# LightLog_SMD_0_6.net
KiCad netlist of a schematic drawn in EAGLE
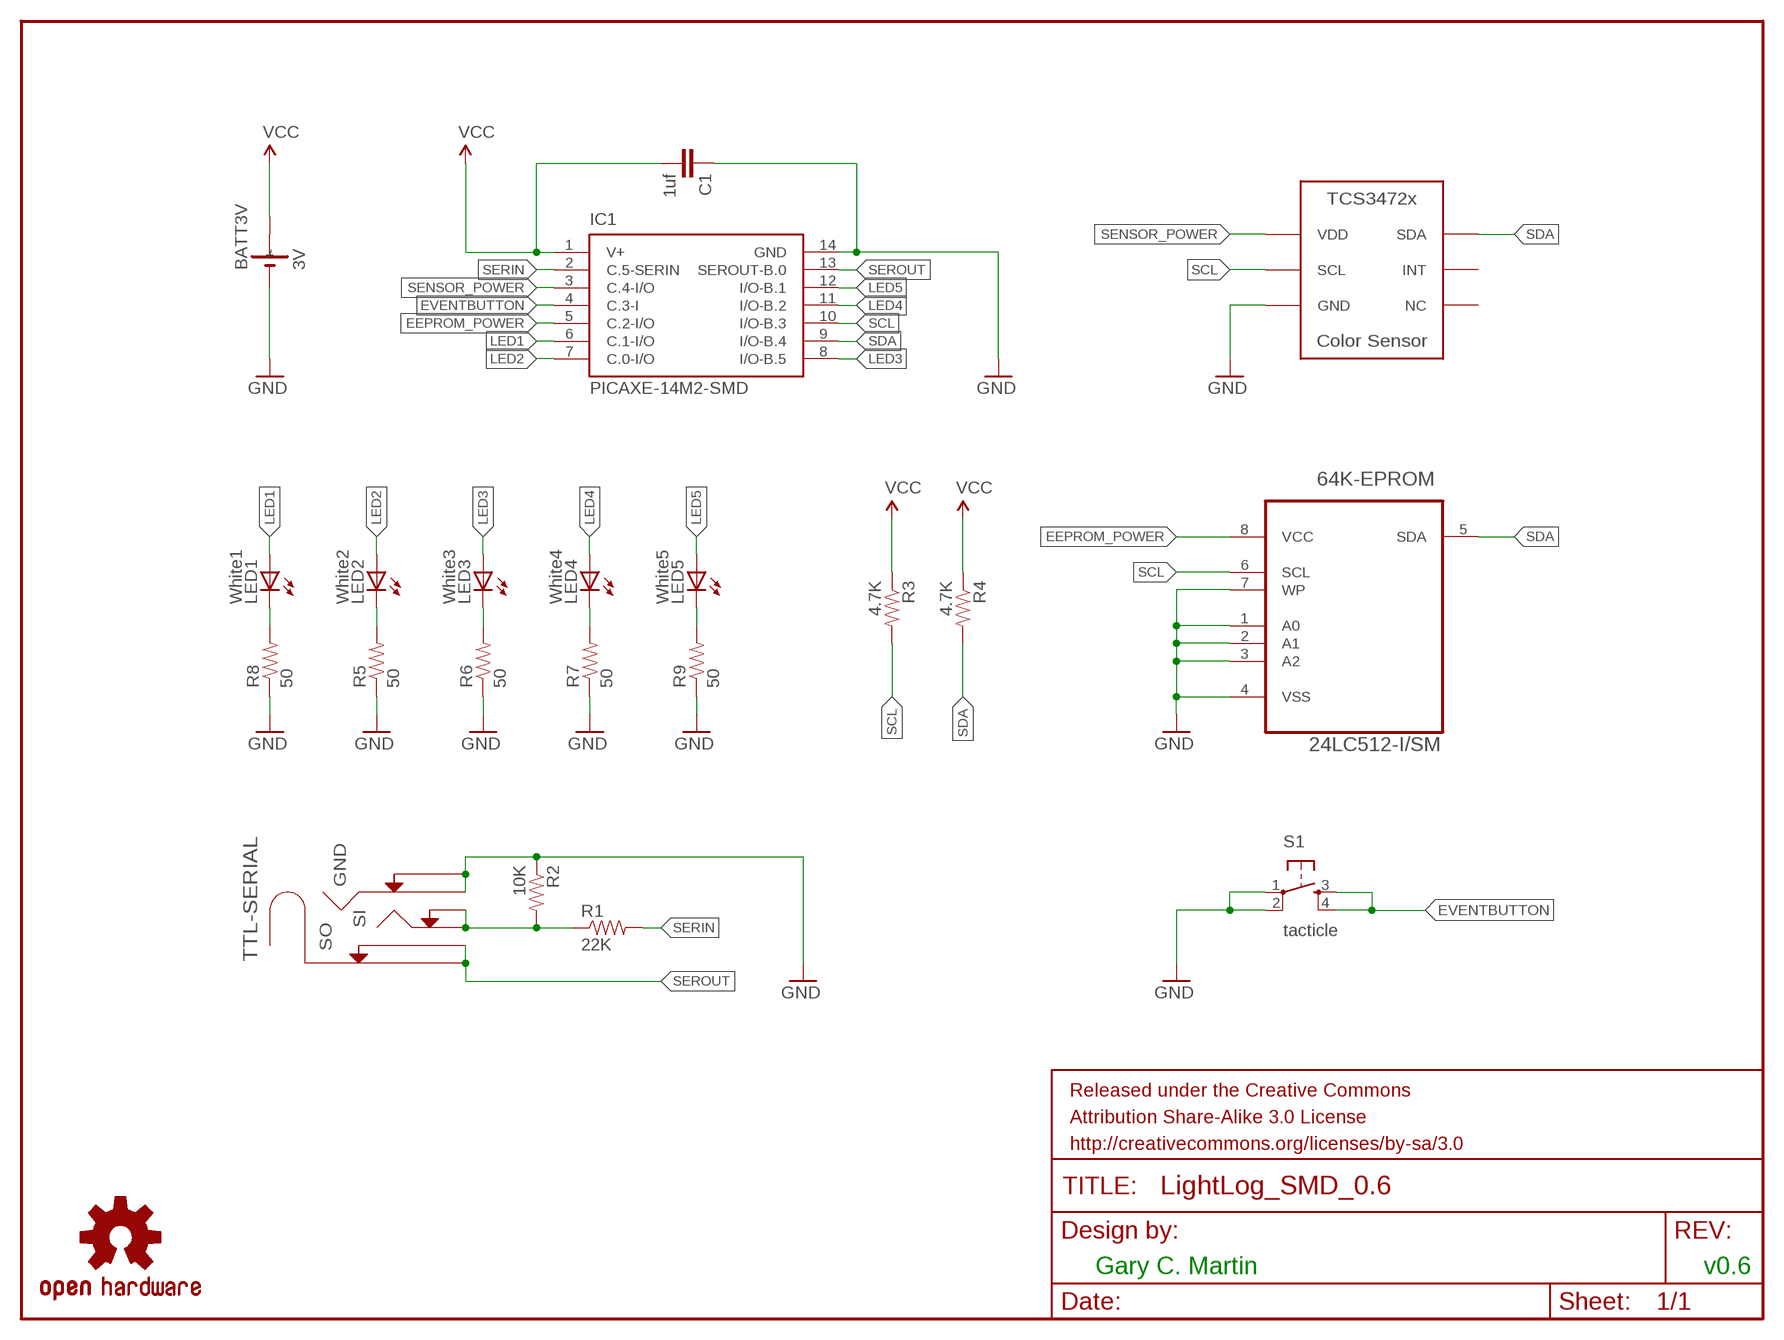
[diagram p0: schematic, sheet 1]

(export (version "E")
  (design (tool "Eeschema 10.0.6"))
  (components
    (comp (ref "64K-EPROM")
      (value "24LC512-I/SM")
      (footprint "eagle-import:SOIC127P794X203-8N")
      (libsource (lib "eagle-import") (part "24LC512-I/SM"))
    )
    (comp (ref "BATT3V")
      (value "3V")
      (footprint "eagle-import:BAT-HLD-001-CR2032-SMD")
      (libsource (lib "eagle-import") (part "BAT-HLD-001-CR2032"))
    )
    (comp (ref "C1")
      (value "1uf")
      (footprint "eagle-import:0805")
      (libsource (lib "eagle-import") (part "CAP0805"))
    )
    (comp (ref "IC1")
      (value "PICAXE-14M2-SMD")
      (footprint "eagle-import:SOIC14")
      (libsource (lib "eagle-import") (part "PICAXE-14M2-SMD"))
    )
    (comp (ref "LED1")
      (value "White1")
      (footprint "eagle-import:LED-1206")
      (libsource (lib "eagle-import") (part "LED1206"))
    )
    (comp (ref "LED2")
      (value "White2")
      (footprint "eagle-import:LED-1206")
      (libsource (lib "eagle-import") (part "LED1206"))
    )
    (comp (ref "LED3")
      (value "White3")
      (footprint "eagle-import:LED-1206")
      (libsource (lib "eagle-import") (part "LED1206"))
    )
    (comp (ref "LED4")
      (value "White4")
      (footprint "eagle-import:LED-1206")
      (libsource (lib "eagle-import") (part "LED1206"))
    )
    (comp (ref "LED5")
      (value "White5")
      (footprint "eagle-import:LED-1206")
      (libsource (lib "eagle-import") (part "LED1206"))
    )
    (comp (ref "LOGO1")
      (value "OSHW-LOGOS")
      (footprint "eagle-import:OSHW-LOGO-S")
      (libsource (lib "eagle-import") (part "OSHW-LOGOS"))
    )
    (comp (ref "R1")
      (value "22K")
      (footprint "eagle-import:0805")
      (libsource (lib "eagle-import") (part "RESISTOR0805-RES"))
    )
    (comp (ref "R2")
      (value "10K")
      (footprint "eagle-import:0805")
      (libsource (lib "eagle-import") (part "RESISTOR0805-RES"))
    )
    (comp (ref "R3")
      (value "4.7K")
      (footprint "eagle-import:0805")
      (libsource (lib "eagle-import") (part "RESISTOR0805-RES"))
    )
    (comp (ref "R4")
      (value "4.7K")
      (footprint "eagle-import:0805")
      (libsource (lib "eagle-import") (part "RESISTOR0805-RES"))
    )
    (comp (ref "R5")
      (value "50")
      (footprint "eagle-import:0805")
      (libsource (lib "eagle-import") (part "RESISTOR0805-RES"))
    )
    (comp (ref "R6")
      (value "50")
      (footprint "eagle-import:0805")
      (libsource (lib "eagle-import") (part "RESISTOR0805-RES"))
    )
    (comp (ref "R7")
      (value "50")
      (footprint "eagle-import:0805")
      (libsource (lib "eagle-import") (part "RESISTOR0805-RES"))
    )
    (comp (ref "R8")
      (value "50")
      (footprint "eagle-import:0805")
      (libsource (lib "eagle-import") (part "RESISTOR0805-RES"))
    )
    (comp (ref "R9")
      (value "50")
      (footprint "eagle-import:0805")
      (libsource (lib "eagle-import") (part "RESISTOR0805-RES"))
    )
    (comp (ref "S1")
      (value "tacticle")
      (footprint "eagle-import:TACTILE_SWITCH_SMD")
      (libsource (lib "eagle-import") (part "TAC_SWITCHSMD"))
    )
    (comp (ref "TTL-SERIAL")
      (value "3-5MM-STEREO-SOCKET")
      (footprint "eagle-import:3-5MM-SMT")
      (libsource (lib "eagle-import") (part "3-5MM-STEREO-SOCKET"))
    )
    (comp (ref "U$1")
      (value "TCS3472")
      (footprint "eagle-import:DUAL-FLAT-NO-LEAD-6PIN")
      (libsource (lib "eagle-import") (part "TCS3472"))
    )
  )
  (nets
    (net (code "1") (name "EEPROM_POWER") (class "Default")
      (node (ref "64K-EPROM") (pin "8") (pinfunction "VCC_8") (pintype "power_in"))
      (node (ref "IC1") (pin "5") (pinfunction "C.2-I/O_5") (pintype "bidirectional"))
    )
    (net (code "2") (name "EVENTBUTTON") (class "Default")
      (node (ref "IC1") (pin "4") (pinfunction "C.3-I_4") (pintype "input"))
      (node (ref "S1") (pin "3") (pinfunction "3_3") (pintype "passive"))
      (node (ref "S1") (pin "4") (pinfunction "4_4") (pintype "passive"))
    )
    (net (code "3") (name "GND") (class "Default")
      (node (ref "64K-EPROM") (pin "1") (pinfunction "A0_1") (pintype "input"))
      (node (ref "64K-EPROM") (pin "2") (pinfunction "A1_2") (pintype "input"))
      (node (ref "64K-EPROM") (pin "3") (pinfunction "A2_3") (pintype "input"))
      (node (ref "64K-EPROM") (pin "4") (pinfunction "VSS_4") (pintype "passive"))
      (node (ref "64K-EPROM") (pin "7") (pinfunction "WP_7") (pintype "input"))
      (node (ref "BATT3V") (pin "NEG") (pinfunction "-_NEG") (pintype "passive"))
      (node (ref "C1") (pin "1") (pinfunction "1_1") (pintype "passive"))
      (node (ref "IC1") (pin "14") (pinfunction "GND_14") (pintype "power_in"))
      (node (ref "R2") (pin "1") (pinfunction "1_1") (pintype "passive"))
      (node (ref "R5") (pin "1") (pinfunction "1_1") (pintype "passive"))
      (node (ref "R6") (pin "1") (pinfunction "1_1") (pintype "passive"))
      (node (ref "R7") (pin "1") (pinfunction "1_1") (pintype "passive"))
      (node (ref "R8") (pin "1") (pinfunction "1_1") (pintype "passive"))
      (node (ref "R9") (pin "1") (pinfunction "1_1") (pintype "passive"))
      (node (ref "S1") (pin "1") (pinfunction "1_1") (pintype "passive"))
      (node (ref "S1") (pin "2") (pinfunction "2_2") (pintype "passive"))
      (node (ref "TTL-SERIAL") (pin "5") (pinfunction "5_5") (pintype "bidirectional"))
      (node (ref "TTL-SERIAL") (pin "6") (pinfunction "6_6") (pintype "bidirectional"))
      (node (ref "U$1") (pin "3") (pinfunction "GND_3") (pintype "bidirectional"))
    )
    (net (code "4") (name "LED1") (class "Default")
      (node (ref "IC1") (pin "6") (pinfunction "C.1-I/O_6") (pintype "bidirectional"))
      (node (ref "LED1") (pin "A") (pinfunction "A_A") (pintype "passive"))
    )
    (net (code "5") (name "LED2") (class "Default")
      (node (ref "IC1") (pin "7") (pinfunction "C.0-I/O_7") (pintype "bidirectional"))
      (node (ref "LED2") (pin "A") (pinfunction "A_A") (pintype "passive"))
    )
    (net (code "6") (name "LED3") (class "Default")
      (node (ref "IC1") (pin "8") (pinfunction "I/O-B.5_8") (pintype "bidirectional"))
      (node (ref "LED3") (pin "A") (pinfunction "A_A") (pintype "passive"))
    )
    (net (code "7") (name "LED4") (class "Default")
      (node (ref "IC1") (pin "11") (pinfunction "I/O-B.2_11") (pintype "bidirectional"))
      (node (ref "LED4") (pin "A") (pinfunction "A_A") (pintype "passive"))
    )
    (net (code "8") (name "LED5") (class "Default")
      (node (ref "IC1") (pin "12") (pinfunction "I/O-B.1_12") (pintype "bidirectional"))
      (node (ref "LED5") (pin "A") (pinfunction "A_A") (pintype "passive"))
    )
    (net (code "9") (name "Net-(LED1-PadC)") (class "Default")
      (node (ref "LED1") (pin "C") (pinfunction "C_C") (pintype "passive"))
      (node (ref "R8") (pin "2") (pinfunction "2_2") (pintype "passive"))
    )
    (net (code "10") (name "Net-(LED2-PadC)") (class "Default")
      (node (ref "LED2") (pin "C") (pinfunction "C_C") (pintype "passive"))
      (node (ref "R5") (pin "2") (pinfunction "2_2") (pintype "passive"))
    )
    (net (code "11") (name "Net-(LED3-PadC)") (class "Default")
      (node (ref "LED3") (pin "C") (pinfunction "C_C") (pintype "passive"))
      (node (ref "R6") (pin "2") (pinfunction "2_2") (pintype "passive"))
    )
    (net (code "12") (name "Net-(LED4-PadC)") (class "Default")
      (node (ref "LED4") (pin "C") (pinfunction "C_C") (pintype "passive"))
      (node (ref "R7") (pin "2") (pinfunction "2_2") (pintype "passive"))
    )
    (net (code "13") (name "Net-(LED5-PadC)") (class "Default")
      (node (ref "LED5") (pin "C") (pinfunction "C_C") (pintype "passive"))
      (node (ref "R9") (pin "2") (pinfunction "2_2") (pintype "passive"))
    )
    (net (code "14") (name "Net-(R1-Pad1)") (class "Default")
      (node (ref "R1") (pin "1") (pinfunction "1_1") (pintype "passive"))
      (node (ref "R2") (pin "2") (pinfunction "2_2") (pintype "passive"))
      (node (ref "TTL-SERIAL") (pin "3") (pinfunction "3_3") (pintype "bidirectional"))
      (node (ref "TTL-SERIAL") (pin "4") (pinfunction "4_4") (pintype "bidirectional"))
    )
    (net (code "15") (name "SCL") (class "Default")
      (node (ref "64K-EPROM") (pin "6") (pinfunction "SCL_6") (pintype "input"))
      (node (ref "IC1") (pin "10") (pinfunction "I/O-B.3_10") (pintype "bidirectional"))
      (node (ref "R3") (pin "2") (pinfunction "2_2") (pintype "passive"))
      (node (ref "U$1") (pin "2") (pinfunction "SCL_2") (pintype "bidirectional"))
    )
    (net (code "16") (name "SDA") (class "Default")
      (node (ref "64K-EPROM") (pin "5") (pinfunction "SDA_5") (pintype "bidirectional"))
      (node (ref "IC1") (pin "9") (pinfunction "I/O-B.4_9") (pintype "bidirectional"))
      (node (ref "R4") (pin "2") (pinfunction "2_2") (pintype "passive"))
      (node (ref "U$1") (pin "6") (pinfunction "SDA_6") (pintype "bidirectional"))
    )
    (net (code "17") (name "SENSOR_POWER") (class "Default")
      (node (ref "IC1") (pin "3") (pinfunction "C.4-I/O_3") (pintype "bidirectional"))
      (node (ref "U$1") (pin "1") (pinfunction "VDD_1") (pintype "bidirectional"))
    )
    (net (code "18") (name "SERIN") (class "Default")
      (node (ref "IC1") (pin "2") (pinfunction "C.5-SERIN_2") (pintype "input"))
      (node (ref "R1") (pin "2") (pinfunction "2_2") (pintype "passive"))
    )
    (net (code "19") (name "SEROUT") (class "Default")
      (node (ref "IC1") (pin "13") (pinfunction "SEROUT-B.0_13") (pintype "output"))
      (node (ref "TTL-SERIAL") (pin "1") (pinfunction "1_1") (pintype "bidirectional"))
      (node (ref "TTL-SERIAL") (pin "2") (pinfunction "2_2") (pintype "bidirectional"))
    )
    (net (code "20") (name "VCC") (class "Default")
      (node (ref "BATT3V") (pin "POS1") (pinfunction "+_POS1") (pintype "passive"))
      (node (ref "C1") (pin "2") (pinfunction "2_2") (pintype "passive"))
      (node (ref "IC1") (pin "1") (pinfunction "V+_1") (pintype "power_in"))
      (node (ref "R3") (pin "1") (pinfunction "1_1") (pintype "passive"))
      (node (ref "R4") (pin "1") (pinfunction "1_1") (pintype "passive"))
    )
    (net (code "21") (name "unconnected-(BATT3V-+-PadPOS2)") (class "Default")
      (node (ref "BATT3V") (pin "POS2") (pinfunction "+_POS2") (pintype "passive"))
    )
    (net (code "22") (name "unconnected-(U$1-INT-Pad5)") (class "Default")
      (node (ref "U$1") (pin "5") (pinfunction "INT_5") (pintype "bidirectional"))
    )
    (net (code "23") (name "unconnected-(U$1-NC-Pad4)") (class "Default")
      (node (ref "U$1") (pin "4") (pinfunction "NC_4") (pintype "bidirectional"))
    )
  )
)
